# Sound_Sensor_Card.net
KiCad netlist of a schematic drawn in EAGLE
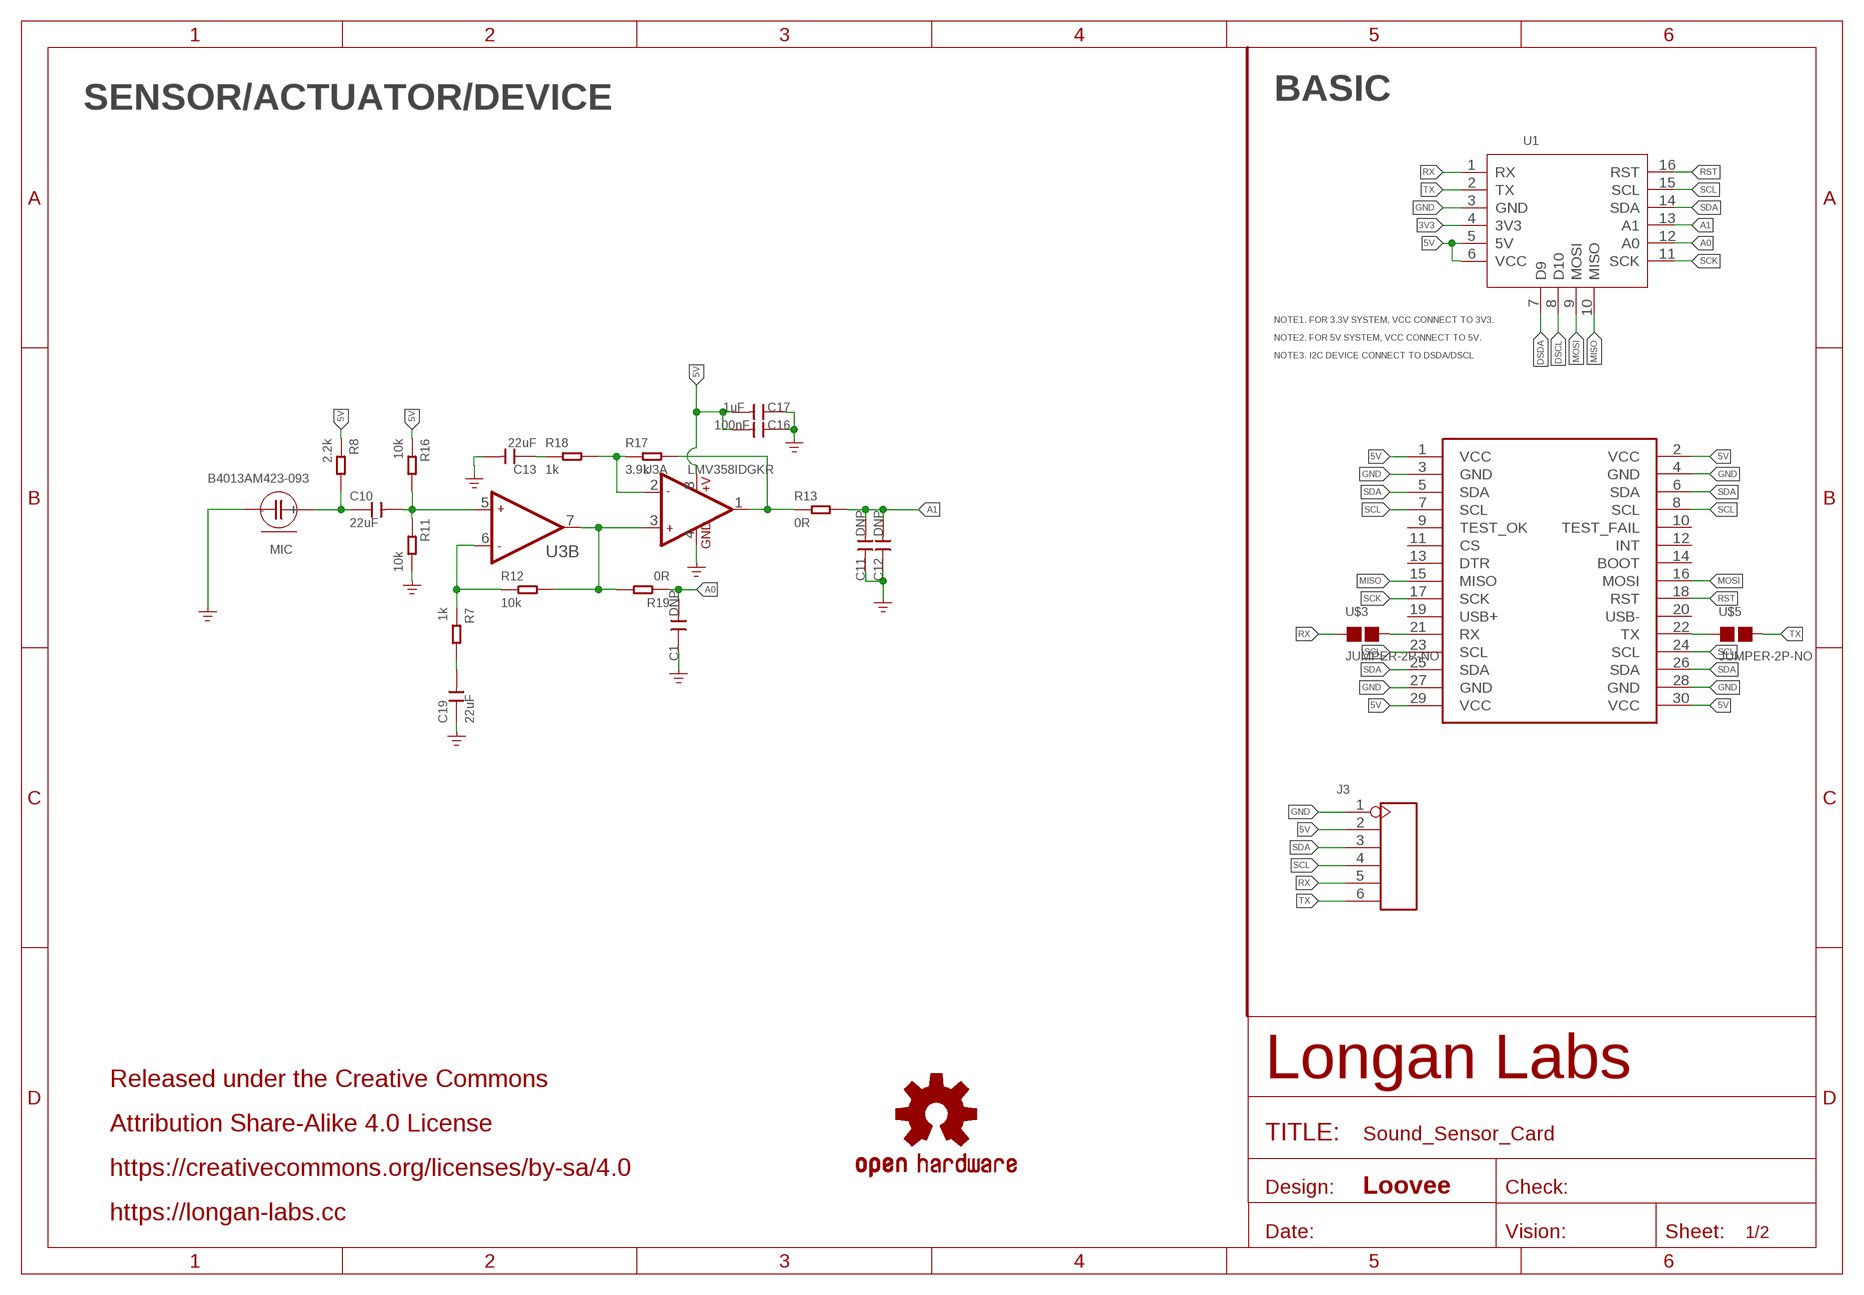
[diagram p0: schematic, sheet 1]

(export (version "E")
  (design (tool "Eeschema 10.0.6"))
  (components
    (comp (ref "C1")
      (value "DNP")
      (footprint "eagle-import:C0603")
      (libsource (lib "eagle-import") (part "CAP-0603"))
    )
    (comp (ref "C10")
      (value "22uF")
      (footprint "eagle-import:C0603")
      (libsource (lib "eagle-import") (part "CAP-0603"))
    )
    (comp (ref "C11")
      (value "DNP")
      (footprint "eagle-import:C0603")
      (libsource (lib "eagle-import") (part "CAP-0603"))
    )
    (comp (ref "C12")
      (value "DNP")
      (footprint "eagle-import:C0603")
      (libsource (lib "eagle-import") (part "CAP-0603"))
    )
    (comp (ref "C13")
      (value "22uF")
      (footprint "eagle-import:C0603")
      (libsource (lib "eagle-import") (part "CAP-0603"))
    )
    (comp (ref "C16")
      (value "100nF")
      (footprint "eagle-import:C0603")
      (libsource (lib "eagle-import") (part "CAP-0603"))
    )
    (comp (ref "C17")
      (value "1uF")
      (footprint "eagle-import:C0603")
      (libsource (lib "eagle-import") (part "CAP-0603"))
    )
    (comp (ref "C19")
      (value "22uF")
      (footprint "eagle-import:C0603")
      (libsource (lib "eagle-import") (part "CAP-0603"))
    )
    (comp (ref "J3")
      (value "HEADER-6P-55/35MIL")
      (footprint "eagle-import:H6-2.54")
      (libsource (lib "eagle-import") (part "HEADER-6P-55/35MIL"))
    )
    (comp (ref "LOGO2")
      (value "OSHW-LOGOS")
      (footprint "eagle-import:OSHW-LOGO-S")
      (libsource (lib "eagle-import") (part "OSHW-LOGOS"))
    )
    (comp (ref "MIC")
      (value "B4013AM423-093")
      (footprint "eagle-import:MIC2P-SMD-4X4X1.3MM")
      (libsource (lib "eagle-import") (part "MICROPHONE-2P-B4013AM423-093"))
    )
    (comp (ref "MOUDLE1")
      (value "MOUDLE-2X15P-2.54'BOARD'")
      (footprint "eagle-import:MOUDLE-2X15P-2.54")
      (libsource (lib "eagle-import") (part "MOUDLE-2X15P-2.54'BOARD'"))
    )
    (comp (ref "R7")
      (value "1k")
      (footprint "eagle-import:R0603")
      (libsource (lib "eagle-import") (part "RES-0603"))
    )
    (comp (ref "R8")
      (value "2.2k")
      (footprint "eagle-import:R0603")
      (libsource (lib "eagle-import") (part "RES-0603"))
    )
    (comp (ref "R11")
      (value "10k")
      (footprint "eagle-import:R0603")
      (libsource (lib "eagle-import") (part "RES-0603"))
    )
    (comp (ref "R12")
      (value "10k")
      (footprint "eagle-import:R0603")
      (libsource (lib "eagle-import") (part "RES-0603"))
    )
    (comp (ref "R13")
      (value "0R")
      (footprint "eagle-import:R0603")
      (libsource (lib "eagle-import") (part "RES-0603"))
    )
    (comp (ref "R16")
      (value "10k")
      (footprint "eagle-import:R0603")
      (libsource (lib "eagle-import") (part "RES-0603"))
    )
    (comp (ref "R17")
      (value "3.9k")
      (footprint "eagle-import:R0603")
      (libsource (lib "eagle-import") (part "RES-0603"))
    )
    (comp (ref "R18")
      (value "1k")
      (footprint "eagle-import:R0603")
      (libsource (lib "eagle-import") (part "RES-0603"))
    )
    (comp (ref "R19")
      (value "0R")
      (footprint "eagle-import:R0603")
      (libsource (lib "eagle-import") (part "RES-0603"))
    )
    (comp (ref "U$3")
      (value "JUMPER-2P-NO")
      (footprint "eagle-import:2P-SMD-NO")
      (libsource (lib "eagle-import") (part "JUMPER-2P-NO"))
    )
    (comp (ref "U$5")
      (value "JUMPER-2P-NO")
      (footprint "eagle-import:2P-SMD-NO")
      (libsource (lib "eagle-import") (part "JUMPER-2P-NO"))
    )
    (comp (ref "U1")
      (value "MOUDLE-CARDS")
      (footprint "eagle-import:16P-2.0-CARDS")
      (libsource (lib "eagle-import") (part "MOUDLE-CARDS"))
    )
    (comp (ref "U3")
      (value "LMV358IDGKR")
      (footprint "eagle-import:MSOP8-0.65-3X3MM")
      (libsource (lib "eagle-import") (part "AMPLIFIER-LMV358'DGK'"))
    )
  )
  (nets
    (net (code "1") (name "3V3") (class "Default")
      (node (ref "U1") (pin "4") (pinfunction "3V3_4") (pintype "bidirectional"))
    )
    (net (code "2") (name "5V") (class "Default")
      (node (ref "C16") (pin "2") (pinfunction "2_2") (pintype "passive"))
      (node (ref "C17") (pin "2") (pinfunction "2_2") (pintype "passive"))
      (node (ref "J3") (pin "2") (pinfunction "2_2") (pintype "bidirectional"))
      (node (ref "MOUDLE1") (pin "1") (pinfunction "VCC_1") (pintype "bidirectional"))
      (node (ref "MOUDLE1") (pin "2") (pinfunction "VCC_2") (pintype "bidirectional"))
      (node (ref "MOUDLE1") (pin "29") (pinfunction "VCC_29") (pintype "bidirectional"))
      (node (ref "MOUDLE1") (pin "30") (pinfunction "VCC_30") (pintype "bidirectional"))
      (node (ref "R16") (pin "1") (pinfunction "1_1") (pintype "passive"))
      (node (ref "R8") (pin "1") (pinfunction "1_1") (pintype "passive"))
      (node (ref "U1") (pin "5") (pinfunction "5V_5") (pintype "bidirectional"))
      (node (ref "U1") (pin "6") (pinfunction "VCC_6") (pintype "bidirectional"))
      (node (ref "U3") (pin "8") (pinfunction "+V_8") (pintype "power_in"))
    )
    (net (code "3") (name "A0") (class "Default")
      (node (ref "C1") (pin "2") (pinfunction "2_2") (pintype "passive"))
      (node (ref "R19") (pin "1") (pinfunction "1_1") (pintype "passive"))
      (node (ref "U1") (pin "12") (pinfunction "A0_12") (pintype "bidirectional"))
    )
    (net (code "4") (name "A1") (class "Default")
      (node (ref "C11") (pin "2") (pinfunction "2_2") (pintype "passive"))
      (node (ref "C12") (pin "2") (pinfunction "2_2") (pintype "passive"))
      (node (ref "R13") (pin "2") (pinfunction "2_2") (pintype "passive"))
      (node (ref "U1") (pin "13") (pinfunction "A1_13") (pintype "bidirectional"))
    )
    (net (code "5") (name "DSCL") (class "Default")
      (node (ref "U1") (pin "8") (pinfunction "D10_8") (pintype "bidirectional"))
    )
    (net (code "6") (name "DSDA") (class "Default")
      (node (ref "U1") (pin "7") (pinfunction "D9_7") (pintype "bidirectional"))
    )
    (net (code "7") (name "GND") (class "Default")
      (node (ref "C1") (pin "1") (pinfunction "1_1") (pintype "passive"))
      (node (ref "C11") (pin "1") (pinfunction "1_1") (pintype "passive"))
      (node (ref "C12") (pin "1") (pinfunction "1_1") (pintype "passive"))
      (node (ref "C13") (pin "2") (pinfunction "2_2") (pintype "passive"))
      (node (ref "C16") (pin "1") (pinfunction "1_1") (pintype "passive"))
      (node (ref "C17") (pin "1") (pinfunction "1_1") (pintype "passive"))
      (node (ref "C19") (pin "1") (pinfunction "1_1") (pintype "passive"))
      (node (ref "J3") (pin "1") (pinfunction "1_1") (pintype "bidirectional"))
      (node (ref "MIC") (pin "-") (pinfunction "-_-") (pintype "bidirectional"))
      (node (ref "MIC") (pin "-1") (pinfunction "-_-1") (pintype "bidirectional"))
      (node (ref "MIC") (pin "-2") (pinfunction "-_-2") (pintype "bidirectional"))
      (node (ref "MIC") (pin "-3") (pinfunction "-_-3") (pintype "bidirectional"))
      (node (ref "MOUDLE1") (pin "27") (pinfunction "GND_27") (pintype "bidirectional"))
      (node (ref "MOUDLE1") (pin "28") (pinfunction "GND_28") (pintype "bidirectional"))
      (node (ref "MOUDLE1") (pin "3") (pinfunction "GND_3") (pintype "bidirectional"))
      (node (ref "MOUDLE1") (pin "4") (pinfunction "GND_4") (pintype "bidirectional"))
      (node (ref "R11") (pin "2") (pinfunction "2_2") (pintype "passive"))
      (node (ref "U1") (pin "3") (pinfunction "GND_3") (pintype "bidirectional"))
      (node (ref "U3") (pin "4") (pinfunction "GND_4") (pintype "power_in"))
    )
    (net (code "8") (name "MISO") (class "Default")
      (node (ref "MOUDLE1") (pin "15") (pinfunction "MISO_15") (pintype "bidirectional"))
      (node (ref "U1") (pin "10") (pinfunction "MISO_10") (pintype "bidirectional"))
    )
    (net (code "9") (name "MOSI") (class "Default")
      (node (ref "MOUDLE1") (pin "16") (pinfunction "MOSI_16") (pintype "bidirectional"))
      (node (ref "U1") (pin "9") (pinfunction "MOSI_9") (pintype "bidirectional"))
    )
    (net (code "10") (name "Net-(C10-Pad1)") (class "Default")
      (node (ref "C10") (pin "1") (pinfunction "1_1") (pintype "passive"))
      (node (ref "MIC") (pin "+") (pinfunction "+_+") (pintype "bidirectional"))
      (node (ref "R8") (pin "2") (pinfunction "2_2") (pintype "passive"))
    )
    (net (code "11") (name "Net-(C13-Pad1)") (class "Default")
      (node (ref "C13") (pin "1") (pinfunction "1_1") (pintype "passive"))
      (node (ref "R18") (pin "1") (pinfunction "1_1") (pintype "passive"))
    )
    (net (code "12") (name "Net-(C19-Pad2)") (class "Default")
      (node (ref "C19") (pin "2") (pinfunction "2_2") (pintype "passive"))
      (node (ref "R7") (pin "2") (pinfunction "2_2") (pintype "passive"))
    )
    (net (code "13") (name "Net-(MOUDLE1-RX)") (class "Default")
      (node (ref "MOUDLE1") (pin "21") (pinfunction "RX_21") (pintype "bidirectional"))
      (node (ref "U$3") (pin "2") (pinfunction "2_2") (pintype "bidirectional"))
    )
    (net (code "14") (name "Net-(MOUDLE1-TX)") (class "Default")
      (node (ref "MOUDLE1") (pin "22") (pinfunction "TX_22") (pintype "bidirectional"))
      (node (ref "U$5") (pin "1") (pinfunction "1_1") (pintype "bidirectional"))
    )
    (net (code "15") (name "Net-(U3A-+IN1)") (class "Default")
      (node (ref "R12") (pin "2") (pinfunction "2_2") (pintype "passive"))
      (node (ref "R19") (pin "2") (pinfunction "2_2") (pintype "passive"))
      (node (ref "U3") (pin "3") (pinfunction "+IN1_3") (pintype "input"))
      (node (ref "U3") (pin "7") (pinfunction "OUT2_7") (pintype "output"))
    )
    (net (code "16") (name "Net-(U3A--IN1)") (class "Default")
      (node (ref "R17") (pin "1") (pinfunction "1_1") (pintype "passive"))
      (node (ref "R18") (pin "2") (pinfunction "2_2") (pintype "passive"))
      (node (ref "U3") (pin "2") (pinfunction "-IN1_2") (pintype "input"))
    )
    (net (code "17") (name "Net-(U3A-OUT1)") (class "Default")
      (node (ref "R13") (pin "1") (pinfunction "1_1") (pintype "passive"))
      (node (ref "R17") (pin "2") (pinfunction "2_2") (pintype "passive"))
      (node (ref "U3") (pin "1") (pinfunction "OUT1_1") (pintype "output"))
    )
    (net (code "18") (name "Net-(U3B-+IN2)") (class "Default")
      (node (ref "C10") (pin "2") (pinfunction "2_2") (pintype "passive"))
      (node (ref "R11") (pin "1") (pinfunction "1_1") (pintype "passive"))
      (node (ref "R16") (pin "2") (pinfunction "2_2") (pintype "passive"))
      (node (ref "U3") (pin "5") (pinfunction "+IN2_5") (pintype "input"))
    )
    (net (code "19") (name "Net-(U3B--IN2)") (class "Default")
      (node (ref "R12") (pin "1") (pinfunction "1_1") (pintype "passive"))
      (node (ref "R7") (pin "1") (pinfunction "1_1") (pintype "passive"))
      (node (ref "U3") (pin "6") (pinfunction "-IN2_6") (pintype "input"))
    )
    (net (code "20") (name "RST") (class "Default")
      (node (ref "MOUDLE1") (pin "18") (pinfunction "RST_18") (pintype "bidirectional"))
      (node (ref "U1") (pin "16") (pinfunction "RST_16") (pintype "bidirectional"))
    )
    (net (code "21") (name "RX") (class "Default")
      (node (ref "J3") (pin "5") (pinfunction "5_5") (pintype "bidirectional"))
      (node (ref "U$3") (pin "1") (pinfunction "1_1") (pintype "bidirectional"))
      (node (ref "U1") (pin "1") (pinfunction "RX_1") (pintype "bidirectional"))
    )
    (net (code "22") (name "SCK") (class "Default")
      (node (ref "MOUDLE1") (pin "17") (pinfunction "SCK_17") (pintype "bidirectional"))
      (node (ref "U1") (pin "11") (pinfunction "SCK_11") (pintype "bidirectional"))
    )
    (net (code "23") (name "SCL") (class "Default")
      (node (ref "J3") (pin "4") (pinfunction "4_4") (pintype "bidirectional"))
      (node (ref "MOUDLE1") (pin "23") (pinfunction "SCL_23") (pintype "bidirectional"))
      (node (ref "MOUDLE1") (pin "24") (pinfunction "SCL_24") (pintype "bidirectional"))
      (node (ref "MOUDLE1") (pin "7") (pinfunction "SCL_7") (pintype "bidirectional"))
      (node (ref "MOUDLE1") (pin "8") (pinfunction "SCL_8") (pintype "bidirectional"))
      (node (ref "U1") (pin "15") (pinfunction "SCL_15") (pintype "bidirectional"))
    )
    (net (code "24") (name "SDA") (class "Default")
      (node (ref "J3") (pin "3") (pinfunction "3_3") (pintype "bidirectional"))
      (node (ref "MOUDLE1") (pin "25") (pinfunction "SDA_25") (pintype "bidirectional"))
      (node (ref "MOUDLE1") (pin "26") (pinfunction "SDA_26") (pintype "bidirectional"))
      (node (ref "MOUDLE1") (pin "5") (pinfunction "SDA_5") (pintype "bidirectional"))
      (node (ref "MOUDLE1") (pin "6") (pinfunction "SDA_6") (pintype "bidirectional"))
      (node (ref "U1") (pin "14") (pinfunction "SDA_14") (pintype "bidirectional"))
    )
    (net (code "25") (name "TX") (class "Default")
      (node (ref "J3") (pin "6") (pinfunction "6_6") (pintype "bidirectional"))
      (node (ref "U$5") (pin "2") (pinfunction "2_2") (pintype "bidirectional"))
      (node (ref "U1") (pin "2") (pinfunction "TX_2") (pintype "bidirectional"))
    )
    (net (code "26") (name "unconnected-(MOUDLE1-BOOT-Pad14)") (class "Default")
      (node (ref "MOUDLE1") (pin "14") (pinfunction "BOOT_14") (pintype "bidirectional"))
    )
    (net (code "27") (name "unconnected-(MOUDLE1-CS-Pad11)") (class "Default")
      (node (ref "MOUDLE1") (pin "11") (pinfunction "CS_11") (pintype "bidirectional"))
    )
    (net (code "28") (name "unconnected-(MOUDLE1-DTR-Pad13)") (class "Default")
      (node (ref "MOUDLE1") (pin "13") (pinfunction "DTR_13") (pintype "bidirectional"))
    )
    (net (code "29") (name "unconnected-(MOUDLE1-INT-Pad12)") (class "Default")
      (node (ref "MOUDLE1") (pin "12") (pinfunction "INT_12") (pintype "bidirectional"))
    )
    (net (code "30") (name "unconnected-(MOUDLE1-TEST_FAIL-Pad10)") (class "Default")
      (node (ref "MOUDLE1") (pin "10") (pinfunction "TEST_FAIL_10") (pintype "bidirectional"))
    )
    (net (code "31") (name "unconnected-(MOUDLE1-TEST_OK-Pad9)") (class "Default")
      (node (ref "MOUDLE1") (pin "9") (pinfunction "TEST_OK_9") (pintype "bidirectional"))
    )
    (net (code "32") (name "unconnected-(MOUDLE1-USB+-Pad19)") (class "Default")
      (node (ref "MOUDLE1") (pin "19") (pinfunction "USB+_19") (pintype "bidirectional"))
    )
    (net (code "33") (name "unconnected-(MOUDLE1-USB--Pad20)") (class "Default")
      (node (ref "MOUDLE1") (pin "20") (pinfunction "USB-_20") (pintype "bidirectional"))
    )
  )
)
